# TopLevel.net
KiCad netlist of a schematic drawn in Altium Designer
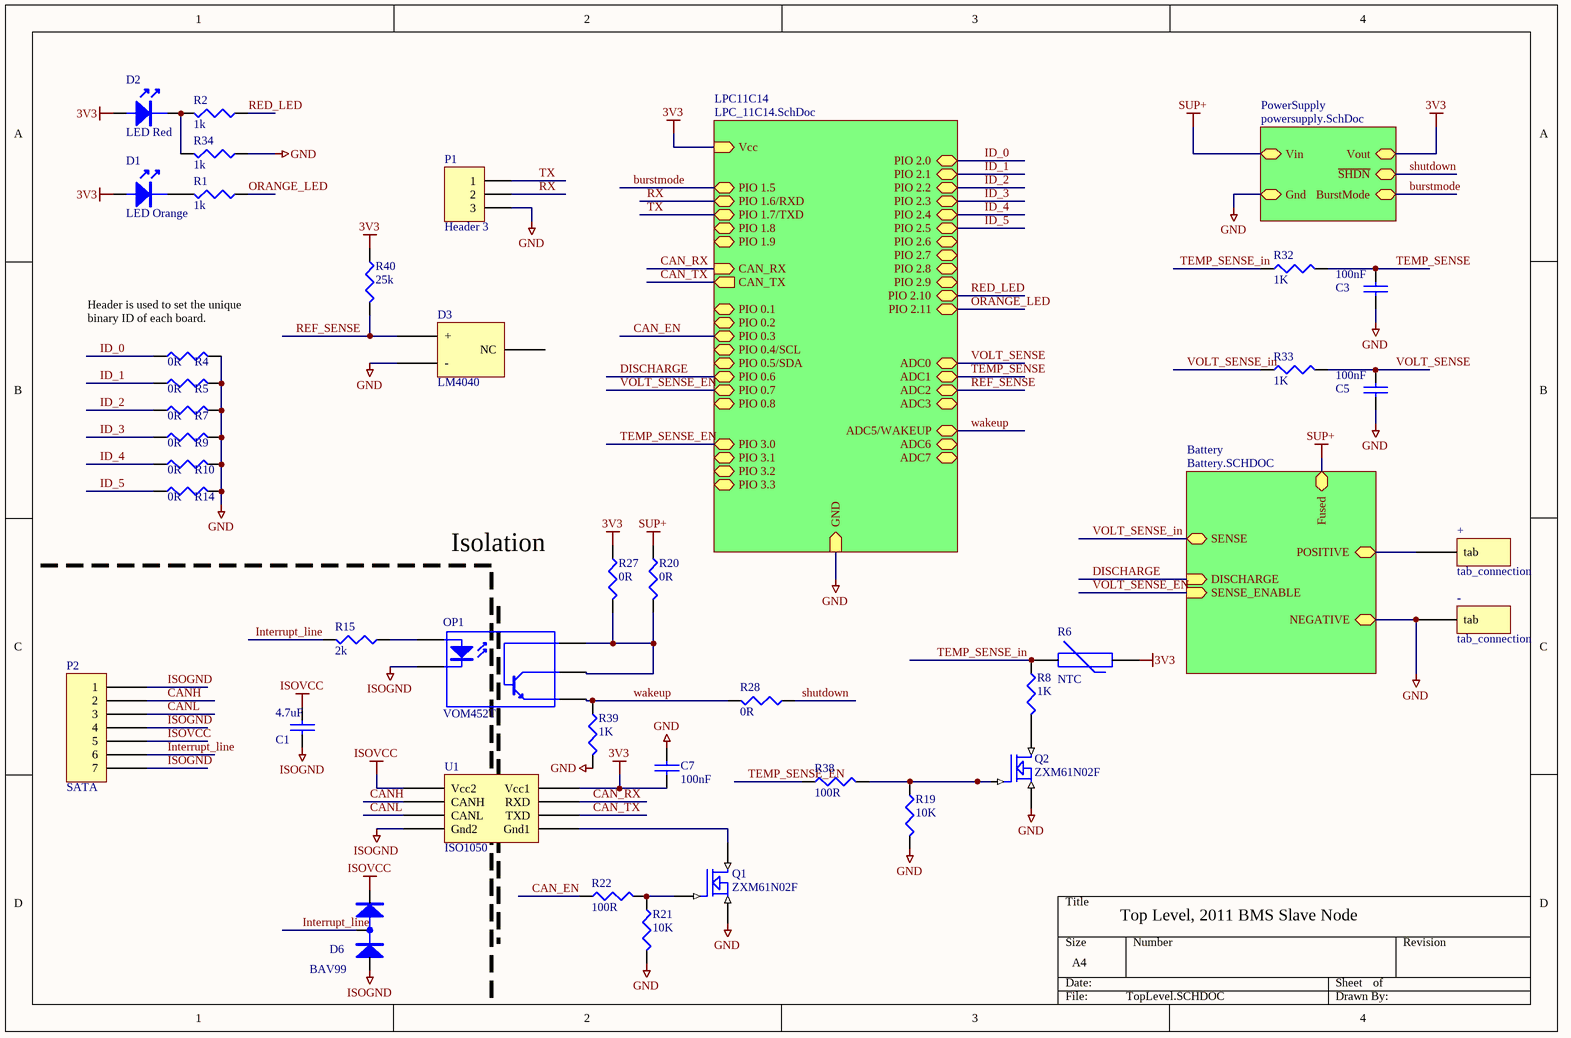
[diagram p0: TopLevel.SCHDOC]

(export (version "E")
  (design (tool "Eeschema 10.0.6"))
  (components
    (comp (ref "+")
      (value "tab_connection")
      (footprint "tab_connect")
      (libsource (lib "BMS") (part "tab_connection"))
    )
    (comp (ref "-")
      (value "tab_connection")
      (footprint "tab_connect")
      (libsource (lib "BMS") (part "tab_connection"))
    )
    (comp (ref "C1")
      (value "4.7uF")
      (footprint "0805")
      (description "Capacitor")
      (libsource (lib "*") (part "CAP"))
    )
    (comp (ref "C3")
      (value "100nF")
      (footprint "0603")
      (description "Capacitor")
      (libsource (lib "*") (part "CAP"))
    )
    (comp (ref "C5")
      (value "100nF")
      (footprint "0603")
      (description "Capacitor")
      (libsource (lib "*") (part "CAP"))
    )
    (comp (ref "C7")
      (value "100nF")
      (footprint "0603")
      (description "Capacitor")
      (libsource (lib "*") (part "CAP"))
    )
    (comp (ref "D1") (value "LED Orange") (footprint "0603_LED") (libsource (lib "SUNSWIFTLIB") (part "LED")))
    (comp (ref "D2")
      (value "LED Red")
      (footprint "0603_LED")
      (libsource (lib "SunswiftLib20030312RR") (part "LED"))
    )
    (comp (ref "D3") (value "LM4040") (footprint "SOT23-3") (libsource (lib "BMS") (part "LM4040")))
    (comp (ref "D6")
      (value "BAV99")
      (footprint "BAV99")
      (description "diode, series connected")
      (libsource (lib "*") (part "DIODE SERIES 2"))
    )
    (comp (ref "OP1") (value "VOM452T") (footprint "VOM452T") (libsource (lib "BMS") (part "VOM452T")))
    (comp (ref "P1")
      (value "Header 3")
      (footprint "HDR1X3")
      (description "Header, 3-Pin")
      (fields (field (name "PUBLISHER") "Altium Limited"))
      (libsource (lib "Miscellaneous Connectors") (part "Header 3"))
    )
    (comp (ref "P2") (value "SATA") (footprint "47080-4005-SATA") (libsource (lib "BMS") (part "SATA")))
    (comp (ref "Q1")
      (value "ZXM61N02F")
      (footprint "SOT23-3")
      (description "1.7A, 20V N-Channel Enhancement mode FET")
      (libsource (lib "RCLDQ") (part "ZXM61N02F"))
    )
    (comp (ref "Q2")
      (value "ZXM61N02F")
      (footprint "SOT23-3")
      (description "1.7A, 20V N-Channel Enhancement mode FET")
      (libsource (lib "RCLDQ") (part "ZXM61N02F"))
    )
    (comp (ref "R1")
      (value "1k")
      (footprint "0603")
      (description "Resistor")
      (libsource (lib "SunswiftLib20030312RR") (part "RES1"))
    )
    (comp (ref "R2")
      (value "1k")
      (footprint "0603")
      (description "Resistor")
      (libsource (lib "SunswiftLib20030312RR") (part "RES1"))
    )
    (comp (ref "R4")
      (value "0R")
      (footprint "0603")
      (description "Resistor")
      (libsource (lib "SUNSWIFTLIB") (part "RES1"))
    )
    (comp (ref "R5")
      (value "0R")
      (footprint "0603")
      (description "Resistor")
      (libsource (lib "SUNSWIFTLIB") (part "RES1"))
    )
    (comp (ref "R6")
      (value "NTC")
      (footprint "MHDR1X2")
      (description "Thermistor, NTC")
      (libsource (lib "RCLDQ") (part "NTC"))
    )
    (comp (ref "R7")
      (value "0R")
      (footprint "0603")
      (description "Resistor")
      (libsource (lib "SUNSWIFTLIB") (part "RES1"))
    )
    (comp (ref "R8")
      (value "1K")
      (footprint "0603")
      (description "Resistor")
      (libsource (lib "SUNSWIFTLIB") (part "RES1"))
    )
    (comp (ref "R9")
      (value "0R")
      (footprint "0603")
      (description "Resistor")
      (libsource (lib "SUNSWIFTLIB") (part "RES1"))
    )
    (comp (ref "R10")
      (value "0R")
      (footprint "0603")
      (description "Resistor")
      (libsource (lib "SUNSWIFTLIB") (part "RES1"))
    )
    (comp (ref "R14")
      (value "0R")
      (footprint "0603")
      (description "Resistor")
      (libsource (lib "SUNSWIFTLIB") (part "RES1"))
    )
    (comp (ref "R15")
      (value "2k")
      (footprint "0603")
      (description "Resistor")
      (libsource (lib "RCLDQ") (part "RES1"))
    )
    (comp (ref "R19")
      (value "10K")
      (footprint "0603")
      (description "Resistor")
      (libsource (lib "SUNSWIFTLIB") (part "RES1"))
    )
    (comp (ref "R20")
      (value "0R")
      (footprint "0603")
      (description "Resistor")
      (libsource (lib "RCLDQ") (part "RES1"))
    )
    (comp (ref "R21")
      (value "10K")
      (footprint "0603")
      (description "Resistor")
      (libsource (lib "SUNSWIFTLIB") (part "RES1"))
    )
    (comp (ref "R22")
      (value "100R")
      (footprint "0603")
      (description "Resistor")
      (libsource (lib "SUNSWIFTLIB") (part "RES1"))
    )
    (comp (ref "R27")
      (value "0R")
      (footprint "0603")
      (description "Resistor")
      (libsource (lib "RCLDQ") (part "RES1"))
    )
    (comp (ref "R28")
      (value "0R")
      (footprint "0603")
      (description "Resistor")
      (libsource (lib "RCLDQ") (part "RES1"))
    )
    (comp (ref "R32")
      (value "1K")
      (footprint "0603")
      (description "Resistor")
      (libsource (lib "SUNSWIFTLIB") (part "RES1"))
    )
    (comp (ref "R33")
      (value "1K")
      (footprint "0603")
      (description "Resistor")
      (libsource (lib "SUNSWIFTLIB") (part "RES1"))
    )
    (comp (ref "R34")
      (value "1k")
      (footprint "0603")
      (description "Resistor")
      (libsource (lib "SunswiftLib20030312RR") (part "RES1"))
    )
    (comp (ref "R38")
      (value "100R")
      (footprint "0603")
      (description "Resistor")
      (libsource (lib "SUNSWIFTLIB") (part "RES1"))
    )
    (comp (ref "R39")
      (value "1K")
      (footprint "0603")
      (description "Resistor")
      (libsource (lib "RCLDQ") (part "RES1"))
    )
    (comp (ref "R40")
      (value "25k")
      (footprint "0603")
      (description "Resistor")
      (libsource (lib "RCLDQ") (part "RES1"))
    )
    (comp (ref "U1") (value "ISO1050") (footprint "SOP8") (libsource (lib "BMS") (part "ISO1050")))
  )
  (nets
    (net (code "4") (name "/CANH") (class "Default")
      (node (ref "P2") (pin "2") (pinfunction "2_2") (pintype "passive"))
      (node (ref "U1") (pin "7") (pinfunction "CANH_7") (pintype "passive"))
    )
    (net (code "5") (name "/CANL") (class "Default")
      (node (ref "P2") (pin "3") (pinfunction "3_3") (pintype "passive"))
      (node (ref "U1") (pin "6") (pinfunction "CANL_6") (pintype "passive"))
    )
    (net (code "6") (name "/CAN_EN") (class "Default")
      (node (ref "R22") (pin "1") (pinfunction "1_1") (pintype "passive"))
    )
    (net (code "7") (name "/CAN_RX") (class "Default")
      (node (ref "U1") (pin "2") (pinfunction "RXD_2") (pintype "passive"))
    )
    (net (code "8") (name "/CAN_TX") (class "Default")
      (node (ref "U1") (pin "3") (pinfunction "TXD_3") (pintype "passive"))
    )
    (net (code "10") (name "/ID_0") (class "Default")
      (node (ref "R4") (pin "1") (pinfunction "1_1") (pintype "passive"))
    )
    (net (code "11") (name "/ID_1") (class "Default")
      (node (ref "R5") (pin "1") (pinfunction "1_1") (pintype "passive"))
    )
    (net (code "12") (name "/ID_2") (class "Default")
      (node (ref "R7") (pin "1") (pinfunction "1_1") (pintype "passive"))
    )
    (net (code "13") (name "/ID_3") (class "Default")
      (node (ref "R9") (pin "1") (pinfunction "1_1") (pintype "passive"))
    )
    (net (code "14") (name "/ID_4") (class "Default")
      (node (ref "R10") (pin "1") (pinfunction "1_1") (pintype "passive"))
    )
    (net (code "15") (name "/ID_5") (class "Default")
      (node (ref "R14") (pin "1") (pinfunction "1_1") (pintype "passive"))
    )
    (net (code "16") (name "/Interrupt_line") (class "Default")
      (node (ref "D6") (pin "C") (pinfunction "C_C") (pintype "passive"))
      (node (ref "P2") (pin "6") (pinfunction "6_6") (pintype "passive"))
      (node (ref "R15") (pin "2") (pinfunction "2_2") (pintype "passive"))
    )
    (net (code "17") (name "/ORANGE_LED") (class "Default")
      (node (ref "R1") (pin "1") (pinfunction "1_1") (pintype "passive"))
    )
    (net (code "32") (name "/POSITIVE") (class "Default")
      (node (ref "+") (pin "0") (pinfunction "tab_0") (pintype "passive"))
    )
    (net (code "33") (name "/RED_LED") (class "Default")
      (node (ref "R2") (pin "1") (pinfunction "1_1") (pintype "passive"))
    )
    (net (code "34") (name "/REF_SENSE") (class "Default")
      (node (ref "D3") (pin "1") (pinfunction "+_1") (pintype "passive"))
      (node (ref "R40") (pin "2") (pinfunction "2_2") (pintype "passive"))
    )
    (net (code "35") (name "/RX") (class "Default")
      (node (ref "P1") (pin "2") (pinfunction "2_2") (pintype "passive"))
    )
    (net (code "36") (name "/TEMP_SENSE") (class "Default")
      (node (ref "C3") (pin "1") (pinfunction "1_1") (pintype "passive"))
      (node (ref "R32") (pin "2") (pinfunction "2_2") (pintype "passive"))
    )
    (net (code "37") (name "/TEMP_SENSE_EN") (class "Default")
      (node (ref "R38") (pin "1") (pinfunction "1_1") (pintype "passive"))
    )
    (net (code "38") (name "/TEMP_SENSE_in") (class "Default")
      (node (ref "R32") (pin "1") (pinfunction "1_1") (pintype "passive"))
      (node (ref "R6") (pin "1") (pinfunction "1_1") (pintype "passive"))
      (node (ref "R8") (pin "1") (pinfunction "1_1") (pintype "passive"))
    )
    (net (code "39") (name "/TX") (class "Default")
      (node (ref "P1") (pin "1") (pinfunction "1_1") (pintype "passive"))
    )
    (net (code "40") (name "/VOLT_SENSE") (class "Default")
      (node (ref "C5") (pin "1") (pinfunction "1_1") (pintype "passive"))
      (node (ref "R33") (pin "2") (pinfunction "2_2") (pintype "passive"))
    )
    (net (code "42") (name "/VOLT_SENSE_in") (class "Default")
      (node (ref "R33") (pin "1") (pinfunction "1_1") (pintype "passive"))
    )
    (net (code "44") (name "/shutdown") (class "Default")
      (node (ref "R28") (pin "1") (pinfunction "1_1") (pintype "passive"))
    )
    (net (code "45") (name "/wakeup") (class "Default")
      (node (ref "OP1") (pin "4") (pinfunction "E_4") (pintype "passive"))
      (node (ref "R28") (pin "2") (pinfunction "2_2") (pintype "passive"))
      (node (ref "R39") (pin "1") (pinfunction "1_1") (pintype "passive"))
    )
    (net (code "46") (name "3V3") (class "Default")
      (node (ref "C7") (pin "1") (pinfunction "1_1") (pintype "passive"))
      (node (ref "D1") (pin "A") (pinfunction "A_A") (pintype "passive"))
      (node (ref "D2") (pin "A") (pinfunction "A_A") (pintype "passive"))
      (node (ref "R27") (pin "1") (pinfunction "1_1") (pintype "passive"))
      (node (ref "R40") (pin "1") (pinfunction "1_1") (pintype "passive"))
      (node (ref "R6") (pin "2") (pinfunction "2_2") (pintype "passive"))
      (node (ref "U1") (pin "1") (pinfunction "Vcc1_1") (pintype "passive"))
    )
    (net (code "47") (name "GND") (class "Default")
      (node (ref "-") (pin "0") (pinfunction "tab_0") (pintype "passive"))
      (node (ref "C3") (pin "2") (pinfunction "2_2") (pintype "passive"))
      (node (ref "C5") (pin "2") (pinfunction "2_2") (pintype "passive"))
      (node (ref "C7") (pin "2") (pinfunction "2_2") (pintype "passive"))
      (node (ref "D3") (pin "2") (pinfunction "-_2") (pintype "passive"))
      (node (ref "P1") (pin "3") (pinfunction "3_3") (pintype "passive"))
      (node (ref "Q1") (pin "2") (pinfunction "S_2") (pintype "input"))
      (node (ref "Q2") (pin "2") (pinfunction "S_2") (pintype "input"))
      (node (ref "R10") (pin "2") (pinfunction "2_2") (pintype "passive"))
      (node (ref "R14") (pin "2") (pinfunction "2_2") (pintype "passive"))
      (node (ref "R19") (pin "2") (pinfunction "2_2") (pintype "passive"))
      (node (ref "R21") (pin "2") (pinfunction "2_2") (pintype "passive"))
      (node (ref "R34") (pin "1") (pinfunction "1_1") (pintype "passive"))
      (node (ref "R39") (pin "2") (pinfunction "2_2") (pintype "passive"))
      (node (ref "R4") (pin "2") (pinfunction "2_2") (pintype "passive"))
      (node (ref "R5") (pin "2") (pinfunction "2_2") (pintype "passive"))
      (node (ref "R7") (pin "2") (pinfunction "2_2") (pintype "passive"))
      (node (ref "R9") (pin "2") (pinfunction "2_2") (pintype "passive"))
    )
    (net (code "48") (name "ISOGND") (class "Default")
      (node (ref "C1") (pin "2") (pinfunction "2_2") (pintype "passive"))
      (node (ref "D6") (pin "A") (pinfunction "A_A") (pintype "passive"))
      (node (ref "OP1") (pin "3") (pinfunction "K_3") (pintype "passive"))
      (node (ref "P2") (pin "1") (pinfunction "1_1") (pintype "passive"))
      (node (ref "P2") (pin "4") (pinfunction "4_4") (pintype "passive"))
      (node (ref "P2") (pin "7") (pinfunction "7_7") (pintype "passive"))
      (node (ref "U1") (pin "5") (pinfunction "Gnd2_5") (pintype "passive"))
    )
    (net (code "49") (name "ISOVCC") (class "Default")
      (node (ref "C1") (pin "1") (pinfunction "1_1") (pintype "passive"))
      (node (ref "D6") (pin "K") (pinfunction "K_K") (pintype "passive"))
      (node (ref "P2") (pin "5") (pinfunction "5_5") (pintype "passive"))
      (node (ref "U1") (pin "8") (pinfunction "Vcc2_8") (pintype "passive"))
    )
    (net (code "50") (name "Net-(D1-PadK)") (class "Default")
      (node (ref "D1") (pin "K") (pinfunction "K_K") (pintype "passive"))
      (node (ref "R1") (pin "2") (pinfunction "2_2") (pintype "passive"))
    )
    (net (code "51") (name "Net-(D2-PadK)") (class "Default")
      (node (ref "D2") (pin "K") (pinfunction "K_K") (pintype "passive"))
      (node (ref "R2") (pin "2") (pinfunction "2_2") (pintype "passive"))
      (node (ref "R34") (pin "2") (pinfunction "2_2") (pintype "passive"))
    )
    (net (code "52") (name "Net-(OP1-A)") (class "Default")
      (node (ref "OP1") (pin "1") (pinfunction "A_1") (pintype "passive"))
      (node (ref "R15") (pin "1") (pinfunction "1_1") (pintype "passive"))
    )
    (net (code "53") (name "Net-(OP1-C-Pad5)") (class "Default")
      (node (ref "OP1") (pin "5") (pinfunction "C_5") (pintype "passive"))
      (node (ref "OP1") (pin "6") (pinfunction "C_6") (pintype "passive"))
      (node (ref "R20") (pin "2") (pinfunction "2_2") (pintype "passive"))
      (node (ref "R27") (pin "2") (pinfunction "2_2") (pintype "passive"))
    )
    (net (code "54") (name "Net-(Q1-D)") (class "Default")
      (node (ref "Q1") (pin "3") (pinfunction "D_3") (pintype "input"))
      (node (ref "U1") (pin "4") (pinfunction "Gnd1_4") (pintype "passive"))
    )
    (net (code "55") (name "Net-(Q1-G)") (class "Default")
      (node (ref "Q1") (pin "1") (pinfunction "G_1") (pintype "input"))
      (node (ref "R21") (pin "1") (pinfunction "1_1") (pintype "passive"))
      (node (ref "R22") (pin "2") (pinfunction "2_2") (pintype "passive"))
    )
    (net (code "56") (name "Net-(Q2-D)") (class "Default")
      (node (ref "Q2") (pin "3") (pinfunction "D_3") (pintype "input"))
      (node (ref "R8") (pin "2") (pinfunction "2_2") (pintype "passive"))
    )
    (net (code "57") (name "Net-(Q2-G)") (class "Default")
      (node (ref "Q2") (pin "1") (pinfunction "G_1") (pintype "input"))
      (node (ref "R19") (pin "1") (pinfunction "1_1") (pintype "passive"))
      (node (ref "R38") (pin "2") (pinfunction "2_2") (pintype "passive"))
    )
    (net (code "58") (name "SUP+") (class "Default")
      (node (ref "R20") (pin "1") (pinfunction "1_1") (pintype "passive"))
    )
    (net (code "59") (name "unconnected-(D3-NC-Pad3)") (class "Default")
      (node (ref "D3") (pin "3") (pinfunction "NC_3") (pintype "passive"))
    )
  )
)
